# 3v-battery-sensor.net
KiCad netlist of a schematic drawn in EAGLE
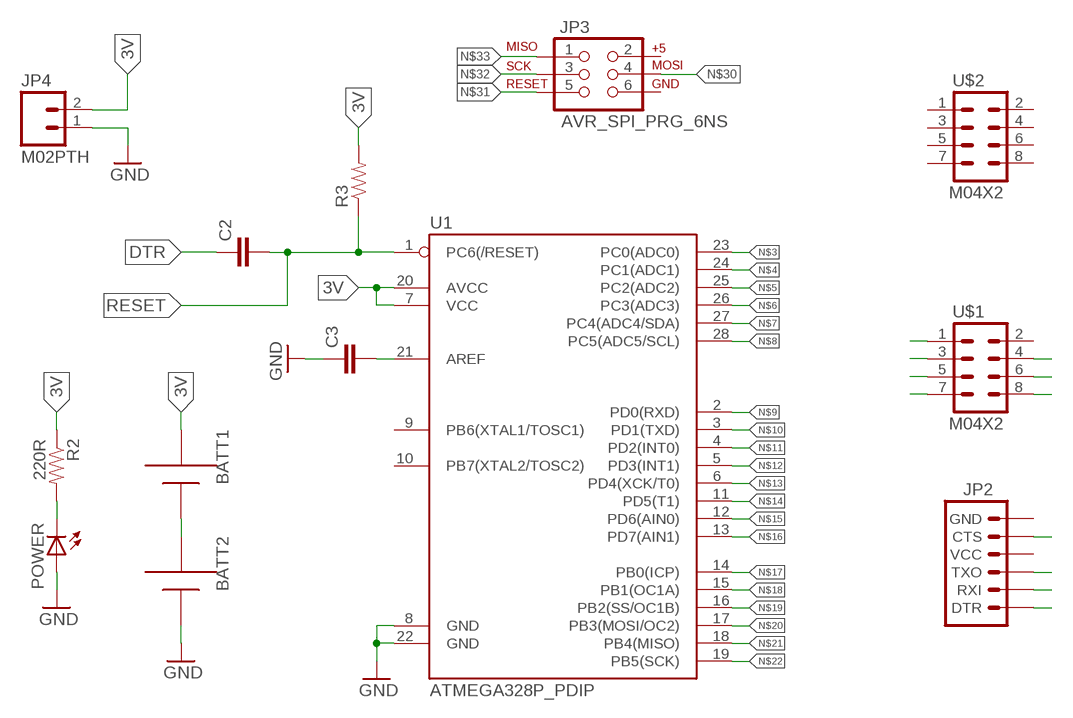
[diagram p0: schematic, sheet 1]

(export (version "E")
  (design (tool "Eeschema 10.0.6"))
  (components
    (comp (ref "BATT1")
      (value "AAA")
      (footprint "eagle-import:12BH412")
      (libsource (lib "eagle-import") (part "AAA"))
    )
    (comp (ref "BATT2")
      (value "AAA")
      (footprint "eagle-import:12BH412")
      (libsource (lib "eagle-import") (part "AAA"))
    )
    (comp (ref "C2")
      (value "CAP0805")
      (footprint "eagle-import:0805")
      (libsource (lib "eagle-import") (part "CAP0805"))
    )
    (comp (ref "C3")
      (value "CAP0805")
      (footprint "eagle-import:0805")
      (libsource (lib "eagle-import") (part "CAP0805"))
    )
    (comp (ref "JP2")
      (value "ARDUINO_SERIAL_PROGRAMPTH")
      (footprint "eagle-import:1X06")
      (libsource (lib "eagle-import") (part "ARDUINO_SERIAL_PROGRAMPTH"))
    )
    (comp (ref "JP3")
      (value "AVR_SPI_PRG_6NS")
      (footprint "eagle-import:2X3-NS")
      (libsource (lib "eagle-import") (part "AVR_SPI_PRG_6NS"))
    )
    (comp (ref "JP4")
      (value "M02PTH")
      (footprint "eagle-import:1X02")
      (libsource (lib "eagle-import") (part "M02PTH"))
    )
    (comp (ref "POWER")
      (value "LEDCHIPLED_0805")
      (footprint "eagle-import:CHIPLED_0805")
      (libsource (lib "eagle-import") (part "LEDCHIPLED_0805"))
    )
    (comp (ref "R2")
      (value "220R")
      (footprint "eagle-import:0805")
      (libsource (lib "eagle-import") (part "RESISTOR0805-RES"))
    )
    (comp (ref "R3")
      (value "RESISTOR0805-RES")
      (footprint "eagle-import:0805")
      (libsource (lib "eagle-import") (part "RESISTOR0805-RES"))
    )
    (comp (ref "U$1")
      (value "M04X2")
      (footprint "eagle-import:2X4")
      (libsource (lib "eagle-import") (part "M04X2"))
    )
    (comp (ref "U$2")
      (value "M04X2")
      (footprint "eagle-import:2X4")
      (libsource (lib "eagle-import") (part "M04X2"))
    )
    (comp (ref "U1")
      (value "ATMEGA328P_PDIP")
      (footprint "eagle-import:DIL28-3")
      (libsource (lib "eagle-import") (part "ATMEGA328P_PDIP"))
    )
  )
  (nets
    (net (code "1") (name "3V") (class "Default")
      (node (ref "BATT1") (pin "-") (pinfunction "-_-") (pintype "bidirectional"))
      (node (ref "JP4") (pin "2") (pinfunction "2_2") (pintype "passive"))
      (node (ref "R2") (pin "1") (pinfunction "1_1") (pintype "passive"))
      (node (ref "R3") (pin "2") (pinfunction "2_2") (pintype "passive"))
      (node (ref "U1") (pin "20") (pinfunction "AVCC_20") (pintype "bidirectional"))
      (node (ref "U1") (pin "7") (pinfunction "VCC_7") (pintype "bidirectional"))
    )
    (net (code "2") (name "DTR") (class "Default")
      (node (ref "C2") (pin "1") (pinfunction "1_1") (pintype "passive"))
    )
    (net (code "3") (name "GND") (class "Default")
      (node (ref "BATT2") (pin "+") (pinfunction "+_+") (pintype "bidirectional"))
      (node (ref "C3") (pin "1") (pinfunction "1_1") (pintype "passive"))
      (node (ref "JP4") (pin "1") (pinfunction "1_1") (pintype "passive"))
      (node (ref "POWER") (pin "A") (pinfunction "A_A") (pintype "passive"))
      (node (ref "U1") (pin "22") (pinfunction "GND_22") (pintype "bidirectional"))
      (node (ref "U1") (pin "8") (pinfunction "GND_8") (pintype "bidirectional"))
    )
    (net (code "4") (name "N$3") (class "Default")
      (node (ref "U1") (pin "23") (pinfunction "PC0(ADC0)_23") (pintype "bidirectional"))
    )
    (net (code "5") (name "N$4") (class "Default")
      (node (ref "U1") (pin "24") (pinfunction "PC1(ADC1)_24") (pintype "bidirectional"))
    )
    (net (code "6") (name "N$5") (class "Default")
      (node (ref "U1") (pin "25") (pinfunction "PC2(ADC2)_25") (pintype "bidirectional"))
    )
    (net (code "7") (name "N$6") (class "Default")
      (node (ref "U1") (pin "26") (pinfunction "PC3(ADC3)_26") (pintype "bidirectional"))
    )
    (net (code "8") (name "N$7") (class "Default")
      (node (ref "U1") (pin "27") (pinfunction "PC4(ADC4/SDA)_27") (pintype "bidirectional"))
    )
    (net (code "9") (name "N$8") (class "Default")
      (node (ref "U1") (pin "28") (pinfunction "PC5(ADC5/SCL)_28") (pintype "bidirectional"))
    )
    (net (code "10") (name "N$9") (class "Default")
      (node (ref "U1") (pin "2") (pinfunction "PD0(RXD)_2") (pintype "bidirectional"))
    )
    (net (code "11") (name "N$10") (class "Default")
      (node (ref "U1") (pin "3") (pinfunction "PD1(TXD)_3") (pintype "bidirectional"))
    )
    (net (code "12") (name "N$11") (class "Default")
      (node (ref "U1") (pin "4") (pinfunction "PD2(INT0)_4") (pintype "bidirectional"))
    )
    (net (code "13") (name "N$12") (class "Default")
      (node (ref "U1") (pin "5") (pinfunction "PD3(INT1)_5") (pintype "bidirectional"))
    )
    (net (code "14") (name "N$13") (class "Default")
      (node (ref "U1") (pin "6") (pinfunction "PD4(XCK/T0)_6") (pintype "bidirectional"))
    )
    (net (code "15") (name "N$14") (class "Default")
      (node (ref "U1") (pin "11") (pinfunction "PD5(T1)_11") (pintype "bidirectional"))
    )
    (net (code "16") (name "N$15") (class "Default")
      (node (ref "U1") (pin "12") (pinfunction "PD6(AIN0)_12") (pintype "bidirectional"))
    )
    (net (code "17") (name "N$16") (class "Default")
      (node (ref "U1") (pin "13") (pinfunction "PD7(AIN1)_13") (pintype "bidirectional"))
    )
    (net (code "18") (name "N$17") (class "Default")
      (node (ref "U1") (pin "14") (pinfunction "PB0(ICP)_14") (pintype "bidirectional"))
    )
    (net (code "19") (name "N$18") (class "Default")
      (node (ref "U1") (pin "15") (pinfunction "PB1(OC1A)_15") (pintype "bidirectional"))
    )
    (net (code "20") (name "N$19") (class "Default")
      (node (ref "U1") (pin "16") (pinfunction "PB2(SS/OC1B)_16") (pintype "bidirectional"))
    )
    (net (code "21") (name "N$20") (class "Default")
      (node (ref "U1") (pin "17") (pinfunction "PB3(MOSI/OC2)_17") (pintype "bidirectional"))
    )
    (net (code "22") (name "N$21") (class "Default")
      (node (ref "U1") (pin "18") (pinfunction "PB4(MISO)_18") (pintype "bidirectional"))
    )
    (net (code "23") (name "N$22") (class "Default")
      (node (ref "U1") (pin "19") (pinfunction "PB5(SCK)_19") (pintype "bidirectional"))
    )
    (net (code "24") (name "N$30") (class "Default")
      (node (ref "JP3") (pin "4") (pinfunction "4_4") (pintype "passive"))
    )
    (net (code "25") (name "N$31") (class "Default")
      (node (ref "JP3") (pin "5") (pinfunction "5_5") (pintype "passive"))
    )
    (net (code "26") (name "N$32") (class "Default")
      (node (ref "JP3") (pin "3") (pinfunction "3_3") (pintype "passive"))
    )
    (net (code "27") (name "N$33") (class "Default")
      (node (ref "JP3") (pin "1") (pinfunction "1_1") (pintype "passive"))
    )
    (net (code "28") (name "Net-(BATT1-Pad+)") (class "Default")
      (node (ref "BATT1") (pin "+") (pinfunction "+_+") (pintype "bidirectional"))
      (node (ref "BATT2") (pin "-") (pinfunction "-_-") (pintype "bidirectional"))
    )
    (net (code "29") (name "Net-(POWER-PadC)") (class "Default")
      (node (ref "POWER") (pin "C") (pinfunction "C_C") (pintype "passive"))
      (node (ref "R2") (pin "2") (pinfunction "2_2") (pintype "passive"))
    )
    (net (code "30") (name "Net-(U1-AREF)") (class "Default")
      (node (ref "C3") (pin "2") (pinfunction "2_2") (pintype "passive"))
      (node (ref "U1") (pin "21") (pinfunction "AREF_21") (pintype "bidirectional"))
    )
    (net (code "31") (name "RESET") (class "Default")
      (node (ref "C2") (pin "2") (pinfunction "2_2") (pintype "passive"))
      (node (ref "R3") (pin "1") (pinfunction "1_1") (pintype "passive"))
      (node (ref "U1") (pin "1") (pinfunction "PC6(/RESET)_1") (pintype "bidirectional"))
    )
    (net (code "32") (name "unconnected-(JP2-CTS-Pad5)") (class "Default")
      (node (ref "JP2") (pin "5") (pinfunction "CTS_5") (pintype "passive"))
    )
    (net (code "33") (name "unconnected-(JP2-DTR-Pad1)") (class "Default")
      (node (ref "JP2") (pin "1") (pinfunction "DTR_1") (pintype "passive"))
    )
    (net (code "34") (name "unconnected-(JP2-GND-Pad6)") (class "Default")
      (node (ref "JP2") (pin "6") (pinfunction "GND_6") (pintype "passive"))
    )
    (net (code "35") (name "unconnected-(JP2-RXI-Pad2)") (class "Default")
      (node (ref "JP2") (pin "2") (pinfunction "RXI_2") (pintype "passive"))
    )
    (net (code "36") (name "unconnected-(JP2-TXO-Pad3)") (class "Default")
      (node (ref "JP2") (pin "3") (pinfunction "TXO_3") (pintype "passive"))
    )
    (net (code "37") (name "unconnected-(JP2-VCC-Pad4)") (class "Default")
      (node (ref "JP2") (pin "4") (pinfunction "VCC_4") (pintype "passive"))
    )
    (net (code "38") (name "unconnected-(JP3-Pad2)") (class "Default")
      (node (ref "JP3") (pin "2") (pinfunction "2_2") (pintype "passive"))
    )
    (net (code "39") (name "unconnected-(JP3-Pad6)") (class "Default")
      (node (ref "JP3") (pin "6") (pinfunction "6_6") (pintype "passive"))
    )
    (net (code "40") (name "unconnected-(U$1-Pad1)") (class "Default")
      (node (ref "U$1") (pin "1") (pinfunction "1_1") (pintype "passive"))
    )
    (net (code "41") (name "unconnected-(U$1-Pad2)") (class "Default")
      (node (ref "U$1") (pin "2") (pinfunction "2_2") (pintype "passive"))
    )
    (net (code "42") (name "unconnected-(U$1-Pad3)") (class "Default")
      (node (ref "U$1") (pin "3") (pinfunction "3_3") (pintype "passive"))
    )
    (net (code "43") (name "unconnected-(U$1-Pad4)") (class "Default")
      (node (ref "U$1") (pin "4") (pinfunction "4_4") (pintype "passive"))
    )
    (net (code "44") (name "unconnected-(U$1-Pad5)") (class "Default")
      (node (ref "U$1") (pin "5") (pinfunction "5_5") (pintype "passive"))
    )
    (net (code "45") (name "unconnected-(U$1-Pad6)") (class "Default")
      (node (ref "U$1") (pin "6") (pinfunction "6_6") (pintype "passive"))
    )
    (net (code "46") (name "unconnected-(U$1-Pad7)") (class "Default")
      (node (ref "U$1") (pin "7") (pinfunction "7_7") (pintype "passive"))
    )
    (net (code "47") (name "unconnected-(U$1-Pad8)") (class "Default")
      (node (ref "U$1") (pin "8") (pinfunction "8_8") (pintype "passive"))
    )
    (net (code "48") (name "unconnected-(U$2-Pad1)") (class "Default")
      (node (ref "U$2") (pin "1") (pinfunction "1_1") (pintype "passive"))
    )
    (net (code "49") (name "unconnected-(U$2-Pad2)") (class "Default")
      (node (ref "U$2") (pin "2") (pinfunction "2_2") (pintype "passive"))
    )
    (net (code "50") (name "unconnected-(U$2-Pad3)") (class "Default")
      (node (ref "U$2") (pin "3") (pinfunction "3_3") (pintype "passive"))
    )
    (net (code "51") (name "unconnected-(U$2-Pad4)") (class "Default")
      (node (ref "U$2") (pin "4") (pinfunction "4_4") (pintype "passive"))
    )
    (net (code "52") (name "unconnected-(U$2-Pad5)") (class "Default")
      (node (ref "U$2") (pin "5") (pinfunction "5_5") (pintype "passive"))
    )
    (net (code "53") (name "unconnected-(U$2-Pad6)") (class "Default")
      (node (ref "U$2") (pin "6") (pinfunction "6_6") (pintype "passive"))
    )
    (net (code "54") (name "unconnected-(U$2-Pad7)") (class "Default")
      (node (ref "U$2") (pin "7") (pinfunction "7_7") (pintype "passive"))
    )
    (net (code "55") (name "unconnected-(U$2-Pad8)") (class "Default")
      (node (ref "U$2") (pin "8") (pinfunction "8_8") (pintype "passive"))
    )
    (net (code "56") (name "unconnected-(U1-PB6(XTAL1{slash}TOSC1)-Pad9)") (class "Default")
      (node (ref "U1") (pin "9") (pinfunction "PB6(XTAL1/TOSC1)_9") (pintype "bidirectional"))
    )
    (net (code "57") (name "unconnected-(U1-PB7(XTAL2{slash}TOSC2)-Pad10)") (class "Default")
      (node (ref "U1") (pin "10") (pinfunction "PB7(XTAL2/TOSC2)_10") (pintype "bidirectional"))
    )
  )
)
